# termistor.net
KiCad netlist of a schematic drawn in EAGLE
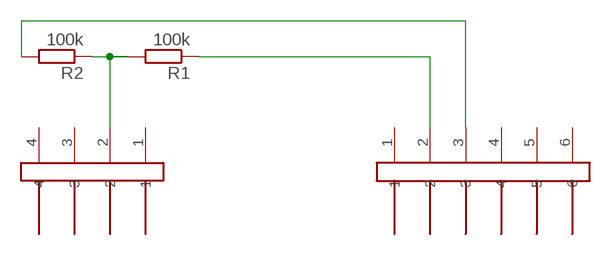
[diagram p0: schematic, sheet 1]

(export (version "E")
  (design (tool "Eeschema 10.0.6"))
  (components
    (comp (ref "R1")
      (value "100k")
      (footprint "eagle-import:R0603")
      (libsource (lib "eagle-import") (part "R-EU_R0603"))
    )
    (comp (ref "R2")
      (value "100k")
      (footprint "eagle-import:R0603")
      (libsource (lib "eagle-import") (part "R-EU_R0603"))
    )
    (comp (ref "U$8")
      (value "JUMPER6M")
      (footprint "eagle-import:JUMPER6M")
      (libsource (lib "eagle-import") (part "JUMPER6M"))
    )
    (comp (ref "U$9")
      (value "JUMPER4M")
      (footprint "eagle-import:JUMPER4M")
      (libsource (lib "eagle-import") (part "JUMPER4M"))
    )
  )
  (nets
    (net (code "1") (name "Net-(R1-Pad1)") (class "Default")
      (node (ref "R1") (pin "1") (pinfunction "1_1") (pintype "passive"))
      (node (ref "U$8") (pin "2") (pinfunction "2_2") (pintype "bidirectional"))
    )
    (net (code "2") (name "Net-(R1-Pad2)") (class "Default")
      (node (ref "R1") (pin "2") (pinfunction "2_2") (pintype "passive"))
      (node (ref "R2") (pin "1") (pinfunction "1_1") (pintype "passive"))
      (node (ref "U$9") (pin "2") (pinfunction "2_2") (pintype "bidirectional"))
    )
    (net (code "3") (name "Net-(R2-Pad2)") (class "Default")
      (node (ref "R2") (pin "2") (pinfunction "2_2") (pintype "passive"))
      (node (ref "U$8") (pin "3") (pinfunction "3_3") (pintype "bidirectional"))
    )
    (net (code "4") (name "unconnected-(U$8-Pad1)") (class "Default")
      (node (ref "U$8") (pin "1") (pinfunction "1_1") (pintype "bidirectional"))
    )
    (net (code "5") (name "unconnected-(U$8-Pad4)") (class "Default")
      (node (ref "U$8") (pin "4") (pinfunction "4_4") (pintype "bidirectional"))
    )
    (net (code "6") (name "unconnected-(U$8-Pad5)") (class "Default")
      (node (ref "U$8") (pin "5") (pinfunction "5_5") (pintype "bidirectional"))
    )
    (net (code "7") (name "unconnected-(U$8-Pad6)") (class "Default")
      (node (ref "U$8") (pin "6") (pinfunction "6_6") (pintype "bidirectional"))
    )
    (net (code "8") (name "unconnected-(U$9-Pad1)") (class "Default")
      (node (ref "U$9") (pin "1") (pinfunction "1_1") (pintype "bidirectional"))
    )
    (net (code "9") (name "unconnected-(U$9-Pad3)") (class "Default")
      (node (ref "U$9") (pin "3") (pinfunction "3_3") (pintype "bidirectional"))
    )
    (net (code "10") (name "unconnected-(U$9-Pad4)") (class "Default")
      (node (ref "U$9") (pin "4") (pinfunction "4_4") (pintype "bidirectional"))
    )
  )
)
